# Current_Sensor.net
KiCad netlist of a schematic drawn in Altium Designer
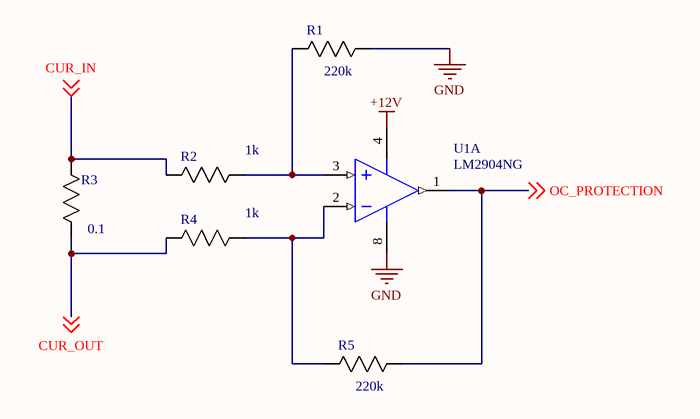
[diagram p0: Current_Sensor.SchDoc]

(export (version "E")
  (design (tool "Eeschema 10.0.6"))
  (components
    (comp (ref "R1")
      (value "AC03000001000JAC00")
      (footprint "RES_AC03_VIS")
      (fields (field (name "TOLERANCE") "5%") (field (name "RESISTANCE") "220k"))
      (libsource (lib "Altium Content Vault") (part "AC03000001000JAC00"))
    )
    (comp (ref "R2")
      (value "AC03000001000JAC00")
      (footprint "RES_AC03_VIS")
      (fields (field (name "TOLERANCE") "5%") (field (name "RESISTANCE") "1k"))
      (libsource (lib "Altium Content Vault") (part "AC03000001000JAC00"))
    )
    (comp (ref "R3")
      (value "AC03000001000JAC00")
      (footprint "RES_AC03_VIS")
      (fields (field (name "TOLERANCE") "5%") (field (name "RESISTANCE") "0.1"))
      (libsource (lib "Altium Content Vault") (part "AC03000001000JAC00"))
    )
    (comp (ref "R4")
      (value "AC03000001000JAC00")
      (footprint "RES_AC03_VIS")
      (fields (field (name "TOLERANCE") "5%") (field (name "RESISTANCE") "1k"))
      (libsource (lib "Altium Content Vault") (part "AC03000001000JAC00"))
    )
    (comp (ref "R5")
      (value "AC03000001000JAC00")
      (footprint "RES_AC03_VIS")
      (fields (field (name "TOLERANCE") "5%") (field (name "RESISTANCE") "220k"))
      (libsource (lib "Altium Content Vault") (part "AC03000001000JAC00"))
    )
    (comp (ref "U1")
      (value "LM2904NG")
      (footprint "ONSC-PDIP-8-626-05_M")
      (description "Single Supply Dual Operational Amplifier, 3 to 32 V, -40 to 105 degC, 8-Pin PDIP, Pb-Free, Tube")
      (fields (field (name "MANUFACTURER") "On Semiconductor"))
      (libsource (lib "Altium Content Vault") (part "ONSC-LM258_2904-8"))
    )
  )
  (nets
    (net (code "1") (name "+12V") (class "Default")
      (node (ref "U1") (pin "4") (pinfunction "VEE/GND_4") (pintype "power_in"))
    )
    (net (code "2") (name "CUR_IN") (class "Default")
      (node (ref "R2") (pin "1") (pinfunction "1_1") (pintype "passive"))
      (node (ref "R3") (pin "2") (pinfunction "2_2") (pintype "passive"))
    )
    (net (code "3") (name "CUR_OUT") (class "Default")
      (node (ref "R3") (pin "1") (pinfunction "1_1") (pintype "passive"))
      (node (ref "R4") (pin "1") (pinfunction "1_1") (pintype "passive"))
    )
    (net (code "4") (name "GND") (class "Default")
      (node (ref "R1") (pin "2") (pinfunction "2_2") (pintype "passive"))
      (node (ref "U1") (pin "8") (pinfunction "VCC_8") (pintype "power_in"))
    )
    (net (code "5") (name "Net-(U1A-INA+)") (class "Default")
      (node (ref "R1") (pin "1") (pinfunction "1_1") (pintype "passive"))
      (node (ref "R2") (pin "2") (pinfunction "2_2") (pintype "passive"))
      (node (ref "U1") (pin "3") (pinfunction "INA+_3") (pintype "input"))
    )
    (net (code "6") (name "Net-(U1A-INA-)") (class "Default")
      (node (ref "R4") (pin "2") (pinfunction "2_2") (pintype "passive"))
      (node (ref "R5") (pin "1") (pinfunction "1_1") (pintype "passive"))
      (node (ref "U1") (pin "2") (pinfunction "INA-_2") (pintype "input"))
    )
    (net (code "7") (name "OC_PROTECTION") (class "Default")
      (node (ref "R5") (pin "2") (pinfunction "2_2") (pintype "passive"))
      (node (ref "U1") (pin "1") (pinfunction "OUTA_1") (pintype "output"))
    )
  )
)
